# SCH_STM32_STEPMOTOR.net
KiCad netlist of a schematic drawn in Altium Designer
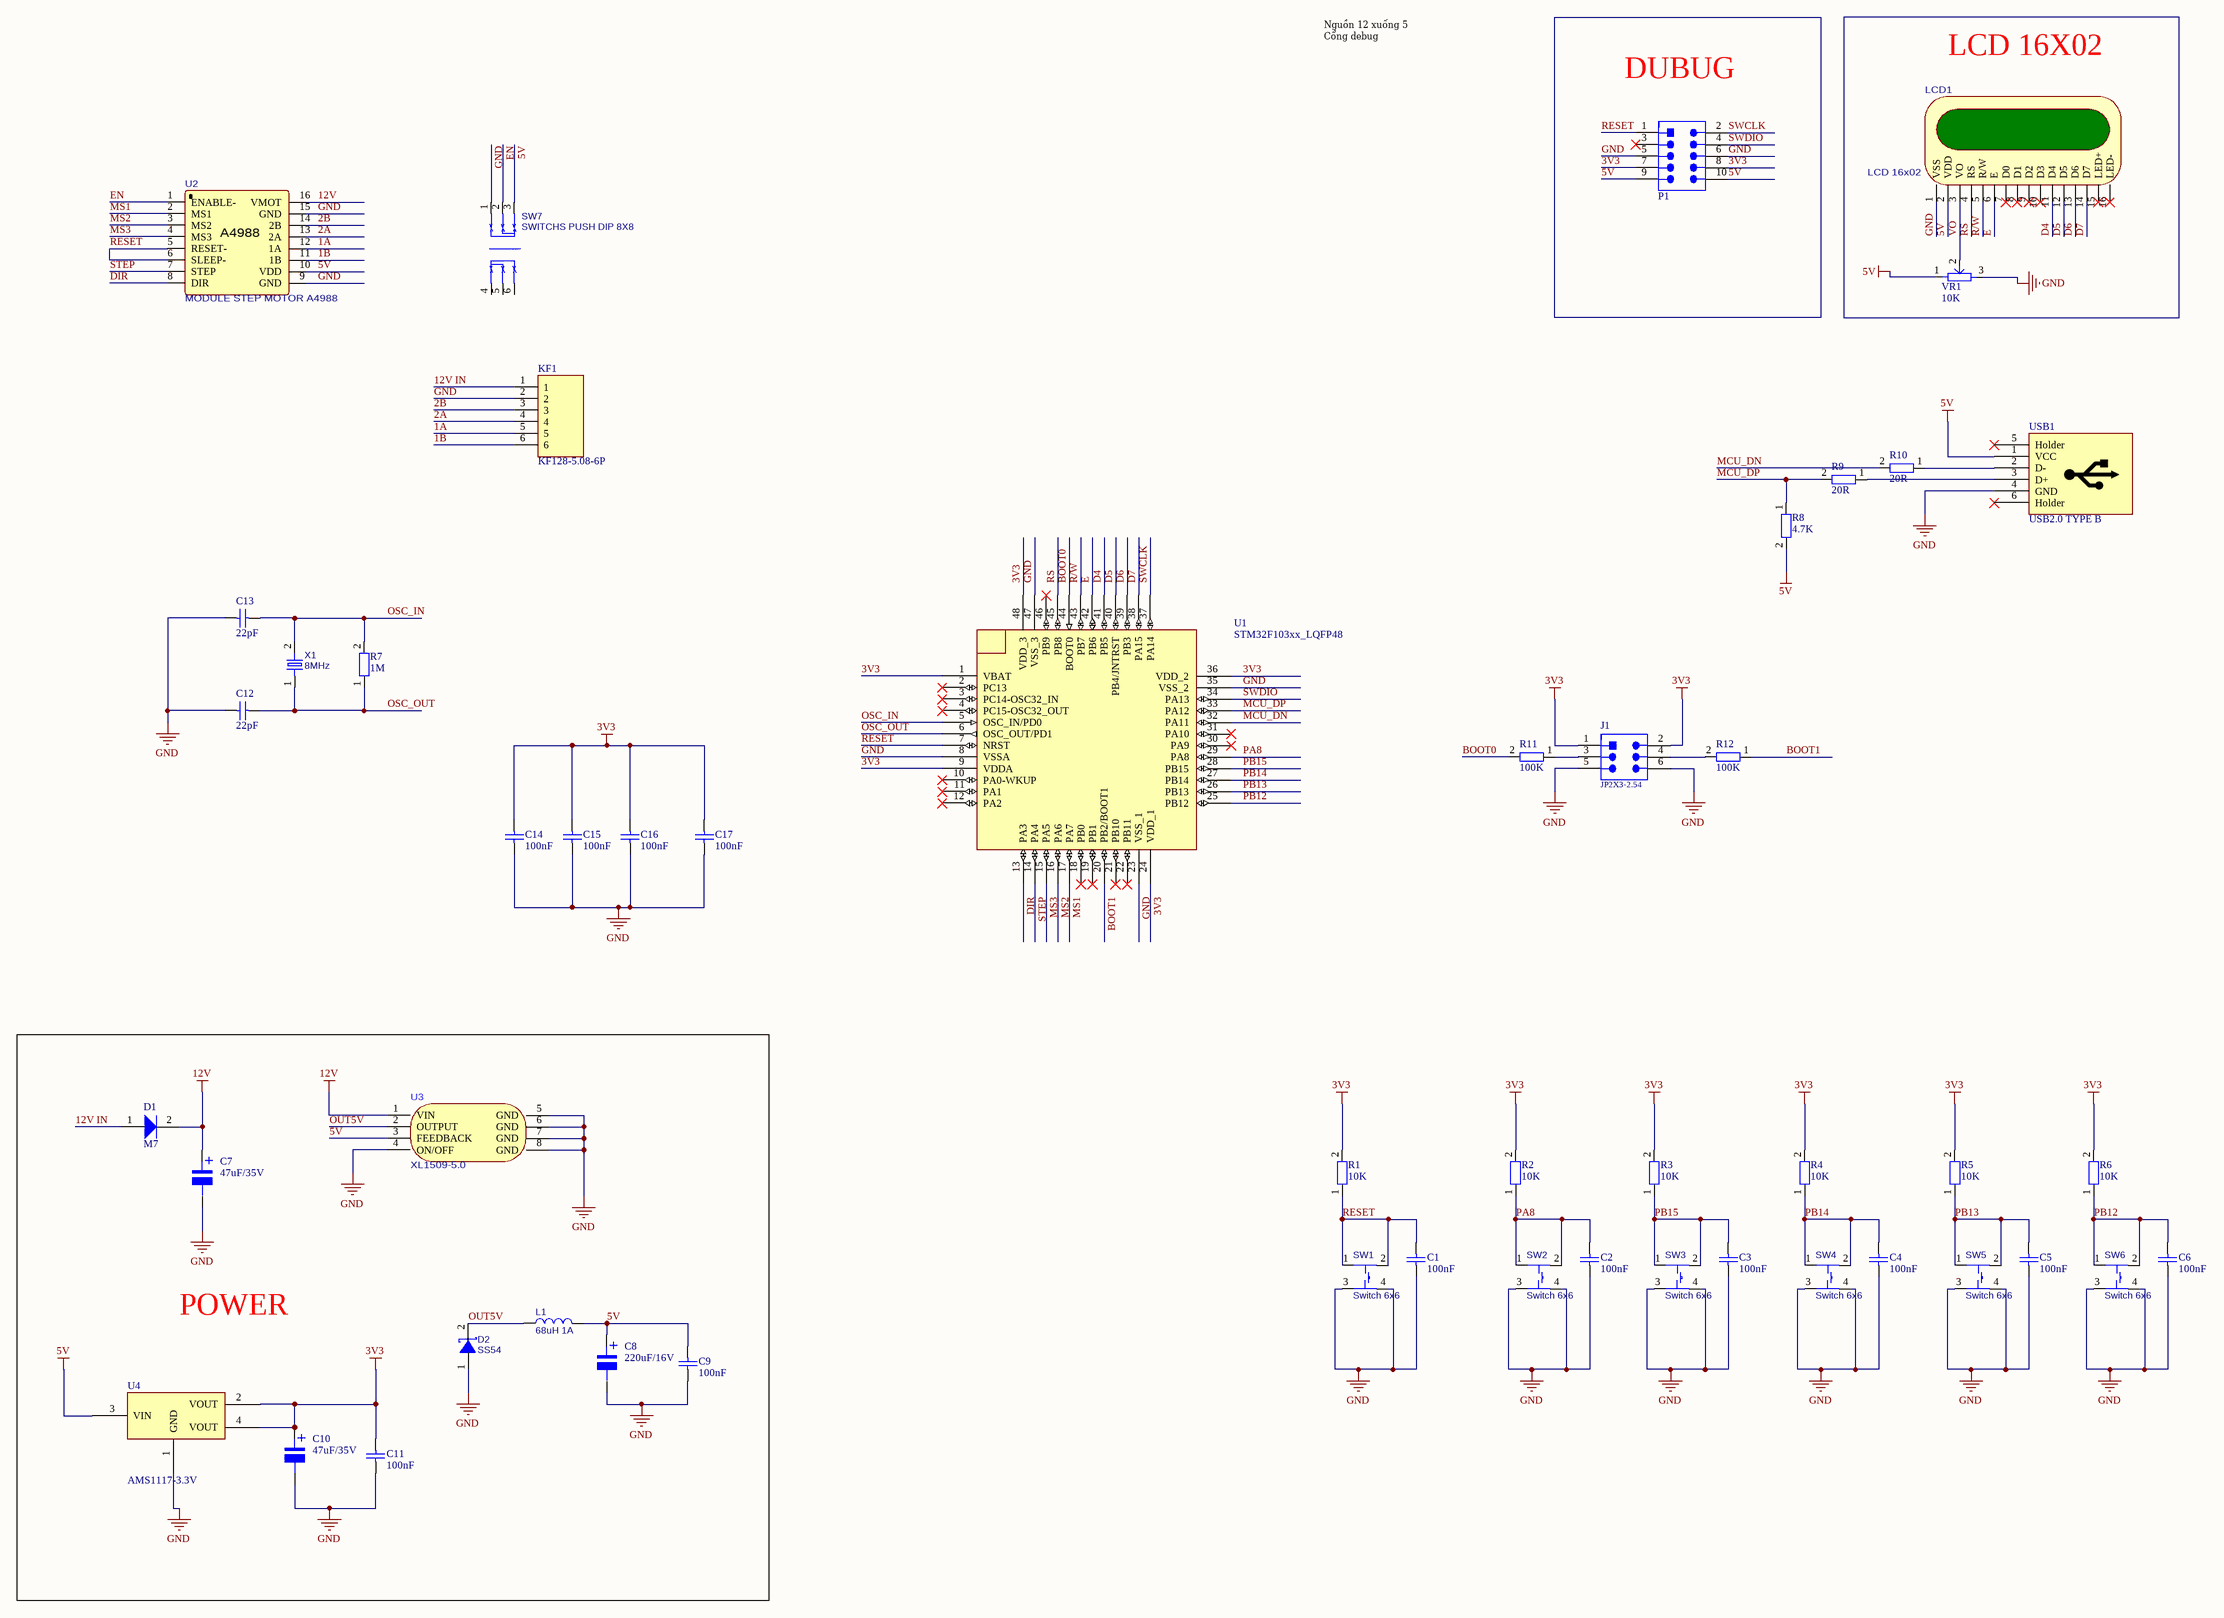
[diagram p0: SCH_STM32_STEPMOTOR.SchDoc]

(export (version "E")
  (design (tool "Eeschema 10.0.6"))
  (components
    (comp (ref "C1")
      (value "100nF")
      (footprint "CAP CERAMIC SMD 0805 TyPE 2012")
      (description "0805 Multilayer Ceramic Capacitors MLCC - SMD/SMT ROHS")
      (libsource (lib "SCH_AES_Library") (part "CAP 0805 50V 10%"))
    )
    (comp (ref "C2")
      (value "100nF")
      (footprint "CAP CERAMIC SMD 0805 TyPE 2012")
      (description "0805 Multilayer Ceramic Capacitors MLCC - SMD/SMT ROHS")
      (libsource (lib "SCH_AES_Library") (part "CAP 0805 50V 10%"))
    )
    (comp (ref "C3")
      (value "100nF")
      (footprint "CAP CERAMIC SMD 0805 TyPE 2012")
      (description "0805 Multilayer Ceramic Capacitors MLCC - SMD/SMT ROHS")
      (libsource (lib "SCH_AES_Library") (part "CAP 0805 50V 10%"))
    )
    (comp (ref "C4")
      (value "100nF")
      (footprint "CAP CERAMIC SMD 0805 TyPE 2012")
      (description "0805 Multilayer Ceramic Capacitors MLCC - SMD/SMT ROHS")
      (libsource (lib "SCH_AES_Library") (part "CAP 0805 50V 10%"))
    )
    (comp (ref "C5")
      (value "100nF")
      (footprint "CAP CERAMIC SMD 0805 TyPE 2012")
      (description "0805 Multilayer Ceramic Capacitors MLCC - SMD/SMT ROHS")
      (libsource (lib "SCH_AES_Library") (part "CAP 0805 50V 10%"))
    )
    (comp (ref "C6")
      (value "100nF")
      (footprint "CAP CERAMIC SMD 0805 TyPE 2012")
      (description "0805 Multilayer Ceramic Capacitors MLCC - SMD/SMT ROHS")
      (libsource (lib "SCH_AES_Library") (part "CAP 0805 50V 10%"))
    )
    (comp (ref "C7")
      (value "47uF/35V")
      (footprint "Cap Alum SMD 6.3x5.4 TYPE D")
      (description "Aluminum Electrolytic Capacitors - SMD ROHS")
      (libsource (lib "SCH_AES_Library") (part "CAP ALUMINUM SMD"))
    )
    (comp (ref "C8")
      (value "220uF/16V")
      (footprint "Cap Alum SMD 6.3x7.7 TYPE D8")
      (description "Aluminum Electrolytic Capacitors - SMD ROHS")
      (libsource (lib "SCH_AES_Library") (part "CAP ALUMINUM SMD"))
    )
    (comp (ref "C9")
      (value "100nF")
      (footprint "CAP CERAMIC SMD 0805 TyPE 2012")
      (description "0805 Multilayer Ceramic Capacitors MLCC - SMD/SMT ROHS")
      (libsource (lib "SCH_AES_Library") (part "CAP 0805 50V 10%"))
    )
    (comp (ref "C10")
      (value "47uF/35V")
      (footprint "Cap Alum SMD 6.3x5.4 TYPE D")
      (description "Aluminum Electrolytic Capacitors - SMD ROHS")
      (libsource (lib "SCH_AES_Library") (part "CAP ALUMINUM SMD"))
    )
    (comp (ref "C11")
      (value "100nF")
      (footprint "CAP CERAMIC SMD 0805 TyPE 2012")
      (description "0805 Multilayer Ceramic Capacitors MLCC - SMD/SMT ROHS")
      (libsource (lib "SCH_AES_Library") (part "CAP 0805 50V 10%"))
    )
    (comp (ref "C12")
      (value "22pF")
      (footprint "CAP CERAMIC SMD 0805 TyPE 2012")
      (description "0805 Multilayer Ceramic Capacitors MLCC - SMD/SMT ROHS")
      (libsource (lib "SCH_AES_Library") (part "CAP 0805 50V 10%"))
    )
    (comp (ref "C13")
      (value "22pF")
      (footprint "CAP CERAMIC SMD 0805 TyPE 2012")
      (description "0805 Multilayer Ceramic Capacitors MLCC - SMD/SMT ROHS")
      (libsource (lib "SCH_AES_Library") (part "CAP 0805 50V 10%"))
    )
    (comp (ref "C14")
      (value "100nF")
      (footprint "CAP CERAMIC SMD 0805 TyPE 2012")
      (description "0805 Multilayer Ceramic Capacitors MLCC - SMD/SMT ROHS")
      (libsource (lib "SCH_AES_Library") (part "CAP 0805 50V 10%"))
    )
    (comp (ref "C15")
      (value "100nF")
      (footprint "CAP CERAMIC SMD 0805 TyPE 2012")
      (description "0805 Multilayer Ceramic Capacitors MLCC - SMD/SMT ROHS")
      (libsource (lib "SCH_AES_Library") (part "CAP 0805 50V 10%"))
    )
    (comp (ref "C16")
      (value "100nF")
      (footprint "CAP CERAMIC SMD 0805 TyPE 2012")
      (description "0805 Multilayer Ceramic Capacitors MLCC - SMD/SMT ROHS")
      (libsource (lib "SCH_AES_Library") (part "CAP 0805 50V 10%"))
    )
    (comp (ref "C17")
      (value "100nF")
      (footprint "CAP CERAMIC SMD 0805 TyPE 2012")
      (description "0805 Multilayer Ceramic Capacitors MLCC - SMD/SMT ROHS")
      (libsource (lib "SCH_AES_Library") (part "CAP 0805 50V 10%"))
    )
    (comp (ref "D1")
      (value "M7")
      (footprint "DIODE SMD SMA")
      (description "1A 1kV Diodes - General Purpose ROHS")
      (libsource (lib "SCH_AES_Library") (part "DIODE SMD 1N4007"))
    )
    (comp (ref "D2")
      (value "SS54")
      (footprint "DO-214AC(SMA)")
      (description "500uA@40V 40V 550mV@5A 5A SMA(DO-214AC) Schottky Barrier Diodes (SBD) ROHS")
      (fields
        (field (name "BOM_SUPPLIER PART") "C478723")
        (field (name "BOM_MANUFACTURER PART") "SS34")
        (field (name "CONTRIBUTOR") "LCSC")
      )
      (libsource (lib "SCH_AES_Library") (part "DIODE SMD SS54"))
    )
    (comp (ref "J1")
      (value "JP2X3-2.54")
      (footprint "CONNECTORS MALE HEADERS 2X3 2.54 TYPE STRAIGHT")
      (description "WR-PHD Pin Header, THT, pitch 2.54mm, Dual Row, Angled, 6p")
      (fields
        (field (name "MANUFACTURER PART NUMBER") "61300621021")
        (field (name "MANUFACTURER") "Wurth Elektronik")
      )
      (libsource (lib "SCH_AES_Library") (part "CONNECTORS MALE HEADERS 2X3 2.54"))
    )
    (comp (ref "KF1")
      (value "KF128-5.08-6P")
      (footprint "CONNECTORS SCREW TERMINAL KF128-5.08-6P")
      (description "2~24 Poles, Screw Type, Horizontal, 5.08 Pitch, 24~12 _AWG_, Terminal Block Connector")
      (fields (field (name "MP") "TB004-508-06GR"))
      (libsource (lib "SCH_AES_Library") (part "CONNECTORS SCREW TERMINAL KF128-5.08-6P"))
    )
    (comp (ref "L1")
      (value "68uH 1A")
      (footprint "INDUCTOS POWER SMD CDRH")
      (fields
        (field (name "BOM_SUPPLIER PART") "C578001")
        (field (name "BOM_MANUFACTURER PART") "SCHF160808H47NJT")
        (field (name "CONTRIBUTOR") "LCSC")
      )
      (libsource (lib "SCH_AES_Library") (part "INDUCTORS SMD"))
    )
    (comp (ref "LCD1")
      (value "LCD 16x02")
      (footprint "LCD DISPLAYS 16X2")
      (description "LCD Displays Modules 16x02 5V ROHS")
      (libsource (lib "SCH_AES_Library") (part "LCD DISPLAYS 16x02"))
    )
    (comp (ref "P1")
      (value "IDE 5X2")
      (footprint "CONNECTORS IDC PUSH PULL 5x2 TYPE STRAIGHT")
      (description "WR-BHD Box Header, Male, pitch 2.54mm, SMT, Straight, 10p")
      (fields
        (field (name "MANUFACTURER") "Wurth Elektronik")
        (field (name "MANUFACTURER PART NUMBER") "61201020621")
      )
      (libsource (lib "SCH_AES_Library") (part "CONNECTORS IDC 5X2"))
    )
    (comp (ref "R1")
      (value "10K")
      (footprint "RES CHIPS SMD 0805 TYPE 2012")
      (description "±1% - Chip Resistor - Surface Mount ROHS")
      (libsource (lib "SCH_AES_Library") (part "RES 0805 1%"))
    )
    (comp (ref "R2")
      (value "10K")
      (footprint "RES CHIPS SMD 0805 TYPE 2012")
      (description "±1% - Chip Resistor - Surface Mount ROHS")
      (libsource (lib "SCH_AES_Library") (part "RES 0805 1%"))
    )
    (comp (ref "R3")
      (value "10K")
      (footprint "RES CHIPS SMD 0805 TYPE 2012")
      (description "±1% - Chip Resistor - Surface Mount ROHS")
      (libsource (lib "SCH_AES_Library") (part "RES 0805 1%"))
    )
    (comp (ref "R4")
      (value "10K")
      (footprint "RES CHIPS SMD 0805 TYPE 2012")
      (description "±1% - Chip Resistor - Surface Mount ROHS")
      (libsource (lib "SCH_AES_Library") (part "RES 0805 1%"))
    )
    (comp (ref "R5")
      (value "10K")
      (footprint "RES CHIPS SMD 0805 TYPE 2012")
      (description "±1% - Chip Resistor - Surface Mount ROHS")
      (libsource (lib "SCH_AES_Library") (part "RES 0805 1%"))
    )
    (comp (ref "R6")
      (value "10K")
      (footprint "RES CHIPS SMD 0805 TYPE 2012")
      (description "±1% - Chip Resistor - Surface Mount ROHS")
      (libsource (lib "SCH_AES_Library") (part "RES 0805 1%"))
    )
    (comp (ref "R7")
      (value "1M")
      (footprint "RES CHIPS SMD 0805 TYPE 2012")
      (description "±1% - Chip Resistor - Surface Mount ROHS")
      (libsource (lib "SCH_AES_Library") (part "RES 0805 1%"))
    )
    (comp (ref "R8")
      (value "4.7K")
      (footprint "RES CHIPS SMD 0805 TYPE 2012")
      (description "±1% - Chip Resistor - Surface Mount ROHS")
      (libsource (lib "SCH_AES_Library") (part "RES 0805 1%"))
    )
    (comp (ref "R9")
      (value "20R")
      (footprint "RES CHIPS SMD 0805 TYPE 2012")
      (description "±1% - Chip Resistor - Surface Mount ROHS")
      (libsource (lib "SCH_AES_Library") (part "RES 0805 1%"))
    )
    (comp (ref "R10")
      (value "20R")
      (footprint "RES CHIPS SMD 0805 TYPE 2012")
      (description "±1% - Chip Resistor - Surface Mount ROHS")
      (libsource (lib "SCH_AES_Library") (part "RES 0805 1%"))
    )
    (comp (ref "R11")
      (value "100K")
      (footprint "RES CHIPS SMD 0805 TYPE 2012")
      (description "±1% - Chip Resistor - Surface Mount ROHS")
      (libsource (lib "SCH_AES_Library") (part "RES 0805 1%"))
    )
    (comp (ref "R12")
      (value "100K")
      (footprint "RES CHIPS SMD 0805 TYPE 2012")
      (description "±1% - Chip Resistor - Surface Mount ROHS")
      (libsource (lib "SCH_AES_Library") (part "RES 0805 1%"))
    )
    (comp (ref "SW1")
      (value "Switch 6x6")
      (footprint "SWITCHES TACTILE DIP 6X6x5 mm")
      (fields
        (field (name "BOM_MANUFACTURER PART") "B3F-1000")
        (field (name "BOM_SUPPLIER PART") "C93157")
        (field (name "CONTRIBUTOR") "LCSC")
      )
      (libsource (lib "SCH_AES_Library") (part "Switches Tactile 6x6mm"))
    )
    (comp (ref "SW2")
      (value "Switch 6x6")
      (footprint "SWITCHES TACTILE DIP 6X6x5 mm")
      (fields
        (field (name "BOM_MANUFACTURER PART") "B3F-1000")
        (field (name "BOM_SUPPLIER PART") "C93157")
        (field (name "CONTRIBUTOR") "LCSC")
      )
      (libsource (lib "SCH_AES_Library") (part "Switches Tactile 6x6mm"))
    )
    (comp (ref "SW3")
      (value "Switch 6x6")
      (footprint "SWITCHES TACTILE DIP 6X6x5 mm")
      (fields
        (field (name "BOM_MANUFACTURER PART") "B3F-1000")
        (field (name "BOM_SUPPLIER PART") "C93157")
        (field (name "CONTRIBUTOR") "LCSC")
      )
      (libsource (lib "SCH_AES_Library") (part "Switches Tactile 6x6mm"))
    )
    (comp (ref "SW4")
      (value "Switch 6x6")
      (footprint "SWITCHES TACTILE DIP 6X6x5 mm")
      (fields
        (field (name "BOM_MANUFACTURER PART") "B3F-1000")
        (field (name "BOM_SUPPLIER PART") "C93157")
        (field (name "CONTRIBUTOR") "LCSC")
      )
      (libsource (lib "SCH_AES_Library") (part "Switches Tactile 6x6mm"))
    )
    (comp (ref "SW5")
      (value "Switch 6x6")
      (footprint "SWITCHES TACTILE DIP 6X6x5 mm")
      (fields
        (field (name "BOM_MANUFACTURER PART") "B3F-1000")
        (field (name "BOM_SUPPLIER PART") "C93157")
        (field (name "CONTRIBUTOR") "LCSC")
      )
      (libsource (lib "SCH_AES_Library") (part "Switches Tactile 6x6mm"))
    )
    (comp (ref "SW6")
      (value "Switch 6x6")
      (footprint "SWITCHES TACTILE DIP 6X6x5 mm")
      (fields
        (field (name "BOM_MANUFACTURER PART") "B3F-1000")
        (field (name "BOM_SUPPLIER PART") "C93157")
        (field (name "CONTRIBUTOR") "LCSC")
      )
      (libsource (lib "SCH_AES_Library") (part "Switches Tactile 6x6mm"))
    )
    (comp (ref "SW7")
      (value "SWITCHS PUSH DIP 8X8")
      (footprint "SWITCHES PUSH DIP 8X8 mm")
      (fields
        (field (name "BOM_SUPPLIER PART") "C318861")
        (field (name "BOM_MANUFACTURER PART") "XKB8080-W")
        (field (name "CONTRIBUTOR") "LCSC")
      )
      (libsource (lib "SCH_AES_Library") (part "SWITCHS PUSH DIP 8X8"))
    )
    (comp (ref "U1")
      (value "STM32F103xx_LQFP48")
      (footprint "LQFP-48")
      (fields (field (name "PUBLISHER") "Altium Limited"))
      (libsource (lib "SCH_AES_Library") (part "MCU_STM32F103xx"))
    )
    (comp (ref "U2")
      (value "MODULE STEP MOTOR A4988")
      (footprint "MODULES STEP MOTOR A4988")
      (description "MODULES STEP MOTOR A4988")
      (libsource (lib "SCH_AES_Library") (part "MODULE STEPMOTOR A4988"))
    )
    (comp (ref "U3")
      (value "XL1509-5.0")
      (footprint "SOP-8")
      (description "SOP-8 DC-DC Converters ROHS")
      (libsource (lib "SCH_AES_Library") (part "POWER CONVERTER XL1509-5.0"))
    )
    (comp (ref "U4")
      (value "AMS1117-3.3V")
      (footprint "SOT-223")
      (description "800mA 1.4V@(1A) Fixed 3.3V~3.3V Positive 1 18V SOT-223 Linear Voltage Regulators (LDO) ROHS")
      (libsource (lib "SCH_AES_Library") (part "POWER CONVERTERS AMS117-3V3"))
    )
    (comp (ref "USB1")
      (value "USB2.0 TYPE B")
      (footprint "CONNECTORS HOLD USB2.0 TYPE B SHRUODED")
      (libsource (lib "SCH_AES_Library") (part "CONNECTORS USB 2.0 DIP TYPE B"))
    )
    (comp (ref "VR1")
      (value "10K")
      (footprint "RES VARIABLE HOLE 3362P")
      (description "Plugin Variable Resistors/Potentiometers ROHS")
      (libsource (lib "SCH_AES_Library") (part "RES VARIABLE DIP"))
    )
    (comp (ref "X1")
      (value "8MHz")
      (footprint "CRYSTALS HOLD HC-49S TYPE 2P")
      (description "Crystals ROHS")
      (fields
        (field (name "BOM_SUPPLIER PART") "C295072")
        (field (name "BOM_MANUFACTURER PART") "XIHCELNANF-12MHZ")
        (field (name "CONTRIBUTOR") "LCSC")
      )
      (libsource (lib "SCH_AES_Library") (part "CRYSTALS 2P"))
    )
  )
  (nets
    (net (code "1") (name "/1A") (class "Default")
      (node (ref "KF1") (pin "5") (pinfunction "5_5") (pintype "passive"))
      (node (ref "U2") (pin "12") (pinfunction "1A_12") (pintype "passive"))
    )
    (net (code "2") (name "/1B") (class "Default")
      (node (ref "KF1") (pin "6") (pinfunction "6_6") (pintype "passive"))
      (node (ref "U2") (pin "11") (pinfunction "1B_11") (pintype "passive"))
    )
    (net (code "3") (name "/2A") (class "Default")
      (node (ref "KF1") (pin "4") (pinfunction "4_4") (pintype "passive"))
      (node (ref "U2") (pin "13") (pinfunction "2A_13") (pintype "passive"))
    )
    (net (code "4") (name "/2B") (class "Default")
      (node (ref "KF1") (pin "3") (pinfunction "3_3") (pintype "passive"))
      (node (ref "U2") (pin "14") (pinfunction "2B_14") (pintype "passive"))
    )
    (net (code "5") (name "/12V IN") (class "Default")
      (node (ref "D1") (pin "1") (pinfunction "A_1") (pintype "passive"))
      (node (ref "KF1") (pin "1") (pinfunction "1_1") (pintype "passive"))
    )
    (net (code "6") (name "/BOOT0") (class "Default")
      (node (ref "R11") (pin "2") (pinfunction "2_2") (pintype "passive"))
      (node (ref "U1") (pin "44") (pinfunction "BOOT0_44") (pintype "input"))
    )
    (net (code "7") (name "/BOOT1") (class "Default")
      (node (ref "R12") (pin "1") (pinfunction "1_1") (pintype "passive"))
      (node (ref "U1") (pin "20") (pinfunction "PB2/BOOT1_20") (pintype "bidirectional"))
    )
    (net (code "8") (name "/D4") (class "Default")
      (node (ref "LCD1") (pin "11") (pinfunction "D4_11") (pintype "passive"))
      (node (ref "U1") (pin "41") (pinfunction "PB5_41") (pintype "bidirectional"))
    )
    (net (code "9") (name "/D5") (class "Default")
      (node (ref "LCD1") (pin "12") (pinfunction "D5_12") (pintype "passive"))
      (node (ref "U1") (pin "40") (pinfunction "PB4/JNTRST_40") (pintype "bidirectional"))
    )
    (net (code "10") (name "/D6") (class "Default")
      (node (ref "LCD1") (pin "13") (pinfunction "D6_13") (pintype "passive"))
      (node (ref "U1") (pin "39") (pinfunction "PB3_39") (pintype "bidirectional"))
    )
    (net (code "11") (name "/D7") (class "Default")
      (node (ref "LCD1") (pin "14") (pinfunction "D7_14") (pintype "passive"))
      (node (ref "U1") (pin "38") (pinfunction "PA15_38") (pintype "bidirectional"))
    )
    (net (code "12") (name "/DIR") (class "Default")
      (node (ref "U1") (pin "13") (pinfunction "PA3_13") (pintype "bidirectional"))
      (node (ref "U2") (pin "8") (pinfunction "DIR_8") (pintype "passive"))
    )
    (net (code "13") (name "/E") (class "Default")
      (node (ref "LCD1") (pin "6") (pinfunction "E_6") (pintype "passive"))
      (node (ref "U1") (pin "42") (pinfunction "PB6_42") (pintype "bidirectional"))
    )
    (net (code "14") (name "/EN") (class "Default")
      (node (ref "SW7") (pin "2") (pinfunction "2_2") (pintype "passive"))
      (node (ref "U2") (pin "1") (pinfunction "ENABLE-_1") (pintype "passive"))
    )
    (net (code "15") (name "/MCU_DN") (class "Default")
      (node (ref "R10") (pin "2") (pinfunction "2_2") (pintype "passive"))
      (node (ref "U1") (pin "32") (pinfunction "PA11_32") (pintype "bidirectional"))
    )
    (net (code "16") (name "/MCU_DP") (class "Default")
      (node (ref "R8") (pin "1") (pinfunction "1_1") (pintype "passive"))
      (node (ref "R9") (pin "2") (pinfunction "2_2") (pintype "passive"))
      (node (ref "U1") (pin "33") (pinfunction "PA12_33") (pintype "bidirectional"))
    )
    (net (code "17") (name "/MS1") (class "Default")
      (node (ref "U1") (pin "17") (pinfunction "PA7_17") (pintype "bidirectional"))
      (node (ref "U2") (pin "2") (pinfunction "MS1_2") (pintype "passive"))
    )
    (net (code "18") (name "/MS2") (class "Default")
      (node (ref "U1") (pin "16") (pinfunction "PA6_16") (pintype "bidirectional"))
      (node (ref "U2") (pin "3") (pinfunction "MS2_3") (pintype "passive"))
    )
    (net (code "19") (name "/MS3") (class "Default")
      (node (ref "U1") (pin "15") (pinfunction "PA5_15") (pintype "bidirectional"))
      (node (ref "U2") (pin "4") (pinfunction "MS3_4") (pintype "passive"))
    )
    (net (code "20") (name "/OSC_IN") (class "Default")
      (node (ref "C13") (pin "1") (pinfunction "1_1") (pintype "passive"))
      (node (ref "R7") (pin "2") (pinfunction "2_2") (pintype "passive"))
      (node (ref "U1") (pin "5") (pinfunction "OSC_IN/PD0_5") (pintype "input"))
      (node (ref "X1") (pin "2") (pinfunction "2_2") (pintype "passive"))
    )
    (net (code "21") (name "/OSC_OUT") (class "Default")
      (node (ref "C12") (pin "1") (pinfunction "1_1") (pintype "passive"))
      (node (ref "R7") (pin "1") (pinfunction "1_1") (pintype "passive"))
      (node (ref "U1") (pin "6") (pinfunction "OSC_OUT/PD1_6") (pintype "output"))
      (node (ref "X1") (pin "1") (pinfunction "1_1") (pintype "passive"))
    )
    (net (code "22") (name "/OUT5V") (class "Default")
      (node (ref "D2") (pin "2") (pinfunction "K_2") (pintype "passive"))
      (node (ref "L1") (pin "1") (pinfunction "1_1") (pintype "passive"))
      (node (ref "U3") (pin "2") (pinfunction "OUTPUT_2") (pintype "passive"))
    )
    (net (code "23") (name "/PA8") (class "Default")
      (node (ref "C2") (pin "1") (pinfunction "1_1") (pintype "passive"))
      (node (ref "R2") (pin "1") (pinfunction "1_1") (pintype "passive"))
      (node (ref "SW2") (pin "1") (pinfunction "1_1") (pintype "passive"))
      (node (ref "SW2") (pin "2") (pinfunction "2_2") (pintype "passive"))
      (node (ref "U1") (pin "29") (pinfunction "PA8_29") (pintype "bidirectional"))
    )
    (net (code "24") (name "/PB12") (class "Default")
      (node (ref "C6") (pin "1") (pinfunction "1_1") (pintype "passive"))
      (node (ref "R6") (pin "1") (pinfunction "1_1") (pintype "passive"))
      (node (ref "SW6") (pin "1") (pinfunction "1_1") (pintype "passive"))
      (node (ref "SW6") (pin "2") (pinfunction "2_2") (pintype "passive"))
      (node (ref "U1") (pin "25") (pinfunction "PB12_25") (pintype "bidirectional"))
    )
    (net (code "25") (name "/PB13") (class "Default")
      (node (ref "C5") (pin "1") (pinfunction "1_1") (pintype "passive"))
      (node (ref "R5") (pin "1") (pinfunction "1_1") (pintype "passive"))
      (node (ref "SW5") (pin "1") (pinfunction "1_1") (pintype "passive"))
      (node (ref "SW5") (pin "2") (pinfunction "2_2") (pintype "passive"))
      (node (ref "U1") (pin "26") (pinfunction "PB13_26") (pintype "bidirectional"))
    )
    (net (code "26") (name "/PB14") (class "Default")
      (node (ref "C4") (pin "1") (pinfunction "1_1") (pintype "passive"))
      (node (ref "R4") (pin "1") (pinfunction "1_1") (pintype "passive"))
      (node (ref "SW4") (pin "1") (pinfunction "1_1") (pintype "passive"))
      (node (ref "SW4") (pin "2") (pinfunction "2_2") (pintype "passive"))
      (node (ref "U1") (pin "27") (pinfunction "PB14_27") (pintype "bidirectional"))
    )
    (net (code "27") (name "/PB15") (class "Default")
      (node (ref "C3") (pin "1") (pinfunction "1_1") (pintype "passive"))
      (node (ref "R3") (pin "1") (pinfunction "1_1") (pintype "passive"))
      (node (ref "SW3") (pin "1") (pinfunction "1_1") (pintype "passive"))
      (node (ref "SW3") (pin "2") (pinfunction "2_2") (pintype "passive"))
      (node (ref "U1") (pin "28") (pinfunction "PB15_28") (pintype "bidirectional"))
    )
    (net (code "28") (name "/RESET") (class "Default")
      (node (ref "C1") (pin "1") (pinfunction "1_1") (pintype "passive"))
      (node (ref "P1") (pin "1") (pinfunction "1_1") (pintype "passive"))
      (node (ref "R1") (pin "1") (pinfunction "1_1") (pintype "passive"))
      (node (ref "SW1") (pin "1") (pinfunction "1_1") (pintype "passive"))
      (node (ref "SW1") (pin "2") (pinfunction "2_2") (pintype "passive"))
      (node (ref "U1") (pin "7") (pinfunction "NRST_7") (pintype "bidirectional"))
      (node (ref "U2") (pin "5") (pinfunction "RESET-_5") (pintype "passive"))
      (node (ref "U2") (pin "6") (pinfunction "SLEEP-_6") (pintype "passive"))
    )
    (net (code "29") (name "/RS") (class "Default")
      (node (ref "LCD1") (pin "4") (pinfunction "RS_4") (pintype "passive"))
      (node (ref "U1") (pin "45") (pinfunction "PB8_45") (pintype "bidirectional"))
    )
    (net (code "30") (name "/R{slash}W") (class "Default")
      (node (ref "LCD1") (pin "5") (pinfunction "R/W_5") (pintype "passive"))
      (node (ref "U1") (pin "43") (pinfunction "PB7_43") (pintype "bidirectional"))
    )
    (net (code "31") (name "/STEP") (class "Default")
      (node (ref "U1") (pin "14") (pinfunction "PA4_14") (pintype "bidirectional"))
      (node (ref "U2") (pin "7") (pinfunction "STEP_7") (pintype "passive"))
    )
    (net (code "32") (name "/SWCLK") (class "Default")
      (node (ref "P1") (pin "2") (pinfunction "2_2") (pintype "passive"))
      (node (ref "U1") (pin "37") (pinfunction "PA14_37") (pintype "bidirectional"))
    )
    (net (code "33") (name "/SWDIO") (class "Default")
      (node (ref "P1") (pin "4") (pinfunction "4_4") (pintype "passive"))
      (node (ref "U1") (pin "34") (pinfunction "PA13_34") (pintype "bidirectional"))
    )
    (net (code "34") (name "/VO") (class "Default")
      (node (ref "LCD1") (pin "3") (pinfunction "VO_3") (pintype "passive"))
      (node (ref "VR1") (pin "2") (pinfunction "2_2") (pintype "passive"))
    )
    (net (code "35") (name "3V3") (class "Default")
      (node (ref "C10") (pin "1") (pinfunction "1_1") (pintype "passive"))
      (node (ref "C11") (pin "1") (pinfunction "1_1") (pintype "passive"))
      (node (ref "C14") (pin "1") (pinfunction "1_1") (pintype "passive"))
      (node (ref "C15") (pin "1") (pinfunction "1_1") (pintype "passive"))
      (node (ref "C16") (pin "1") (pinfunction "1_1") (pintype "passive"))
      (node (ref "C17") (pin "1") (pinfunction "1_1") (pintype "passive"))
      (node (ref "J1") (pin "1") (pinfunction "1_1") (pintype "passive"))
      (node (ref "J1") (pin "2") (pinfunction "2_2") (pintype "passive"))
      (node (ref "P1") (pin "7") (pinfunction "7_7") (pintype "passive"))
      (node (ref "P1") (pin "8") (pinfunction "8_8") (pintype "passive"))
      (node (ref "R1") (pin "2") (pinfunction "2_2") (pintype "passive"))
      (node (ref "R2") (pin "2") (pinfunction "2_2") (pintype "passive"))
      (node (ref "R3") (pin "2") (pinfunction "2_2") (pintype "passive"))
      (node (ref "R4") (pin "2") (pinfunction "2_2") (pintype "passive"))
      (node (ref "R5") (pin "2") (pinfunction "2_2") (pintype "passive"))
      (node (ref "R6") (pin "2") (pinfunction "2_2") (pintype "passive"))
      (node (ref "U1") (pin "1") (pinfunction "VBAT_1") (pintype "power_in"))
      (node (ref "U1") (pin "24") (pinfunction "VDD_1_24") (pintype "power_in"))
      (node (ref "U1") (pin "36") (pinfunction "VDD_2_36") (pintype "power_in"))
      (node (ref "U1") (pin "48") (pinfunction "VDD_3_48") (pintype "power_in"))
      (node (ref "U1") (pin "9") (pinfunction "VDDA_9") (pintype "power_in"))
      (node (ref "U4") (pin "2") (pinfunction "VOUT_2") (pintype "passive"))
      (node (ref "U4") (pin "4") (pinfunction "VOUT_4") (pintype "passive"))
    )
    (net (code "36") (name "5V") (class "Default")
      (node (ref "C8") (pin "1") (pinfunction "1_1") (pintype "passive"))
      (node (ref "C9") (pin "1") (pinfunction "1_1") (pintype "passive"))
      (node (ref "L1") (pin "2") (pinfunction "2_2") (pintype "passive"))
      (node (ref "LCD1") (pin "2") (pinfunction "VDD_2") (pintype "passive"))
      (node (ref "P1") (pin "10") (pinfunction "10_10") (pintype "passive"))
      (node (ref "P1") (pin "9") (pinfunction "9_9") (pintype "passive"))
      (node (ref "R8") (pin "2") (pinfunction "2_2") (pintype "passive"))
      (node (ref "SW7") (pin "3") (pinfunction "3_3") (pintype "passive"))
      (node (ref "U2") (pin "10") (pinfunction "VDD_10") (pintype "passive"))
      (node (ref "U3") (pin "3") (pinfunction "FEEDBACK_3") (pintype "passive"))
      (node (ref "U4") (pin "3") (pinfunction "VIN_3") (pintype "passive"))
      (node (ref "USB1") (pin "1") (pinfunction "VCC_1") (pintype "passive"))
      (node (ref "VR1") (pin "1") (pinfunction "1_1") (pintype "passive"))
    )
    (net (code "37") (name "12V") (class "Default")
      (node (ref "C7") (pin "1") (pinfunction "1_1") (pintype "passive"))
      (node (ref "D1") (pin "2") (pinfunction "K_2") (pintype "passive"))
      (node (ref "U2") (pin "16") (pinfunction "VMOT_16") (pintype "passive"))
      (node (ref "U3") (pin "1") (pinfunction "VIN_1") (pintype "passive"))
    )
    (net (code "38") (name "GND") (class "Default")
      (node (ref "C1") (pin "2") (pinfunction "2_2") (pintype "passive"))
      (node (ref "C10") (pin "2") (pinfunction "2_2") (pintype "passive"))
      (node (ref "C11") (pin "2") (pinfunction "2_2") (pintype "passive"))
      (node (ref "C12") (pin "2") (pinfunction "2_2") (pintype "passive"))
      (node (ref "C13") (pin "2") (pinfunction "2_2") (pintype "passive"))
      (node (ref "C14") (pin "2") (pinfunction "2_2") (pintype "passive"))
      (node (ref "C15") (pin "2") (pinfunction "2_2") (pintype "passive"))
      (node (ref "C16") (pin "2") (pinfunction "2_2") (pintype "passive"))
      (node (ref "C17") (pin "2") (pinfunction "2_2") (pintype "passive"))
      (node (ref "C2") (pin "2") (pinfunction "2_2") (pintype "passive"))
      (node (ref "C3") (pin "2") (pinfunction "2_2") (pintype "passive"))
      (node (ref "C4") (pin "2") (pinfunction "2_2") (pintype "passive"))
      (node (ref "C5") (pin "2") (pinfunction "2_2") (pintype "passive"))
      (node (ref "C6") (pin "2") (pinfunction "2_2") (pintype "passive"))
      (node (ref "C7") (pin "2") (pinfunction "2_2") (pintype "passive"))
      (node (ref "C8") (pin "2") (pinfunction "2_2") (pintype "passive"))
      (node (ref "C9") (pin "2") (pinfunction "2_2") (pintype "passive"))
      (node (ref "D2") (pin "1") (pinfunction "A_1") (pintype "passive"))
      (node (ref "J1") (pin "5") (pinfunction "5_5") (pintype "passive"))
      (node (ref "J1") (pin "6") (pinfunction "6_6") (pintype "passive"))
      (node (ref "KF1") (pin "2") (pinfunction "2_2") (pintype "passive"))
      (node (ref "LCD1") (pin "1") (pinfunction "VSS_1") (pintype "passive"))
      (node (ref "P1") (pin "5") (pinfunction "5_5") (pintype "passive"))
      (node (ref "P1") (pin "6") (pinfunction "6_6") (pintype "passive"))
      (node (ref "SW1") (pin "3") (pinfunction "3_3") (pintype "passive"))
      (node (ref "SW1") (pin "4") (pinfunction "4_4") (pintype "passive"))
      (node (ref "SW2") (pin "3") (pinfunction "3_3") (pintype "passive"))
      (node (ref "SW2") (pin "4") (pinfunction "4_4") (pintype "passive"))
      (node (ref "SW3") (pin "3") (pinfunction "3_3") (pintype "passive"))
      (node (ref "SW3") (pin "4") (pinfunction "4_4") (pintype "passive"))
      (node (ref "SW4") (pin "3") (pinfunction "3_3") (pintype "passive"))
      (node (ref "SW4") (pin "4") (pinfunction "4_4") (pintype "passive"))
      (node (ref "SW5") (pin "3") (pinfunction "3_3") (pintype "passive"))
      (node (ref "SW5") (pin "4") (pinfunction "4_4") (pintype "passive"))
      (node (ref "SW6") (pin "3") (pinfunction "3_3") (pintype "passive"))
      (node (ref "SW6") (pin "4") (pinfunction "4_4") (pintype "passive"))
      (node (ref "SW7") (pin "1") (pinfunction "1_1") (pintype "passive"))
      (node (ref "U1") (pin "23") (pinfunction "VSS_1_23") (pintype "power_in"))
      (node (ref "U1") (pin "35") (pinfunction "VSS_2_35") (pintype "power_in"))
      (node (ref "U1") (pin "47") (pinfunction "VSS_3_47") (pintype "power_in"))
      (node (ref "U1") (pin "8") (pinfunction "VSSA_8") (pintype "power_in"))
      (node (ref "U2") (pin "15") (pinfunction "GND_15") (pintype "passive"))
      (node (ref "U2") (pin "9") (pinfunction "GND_9") (pintype "passive"))
      (node (ref "U3") (pin "4") (pinfunction "ON/OFF_4") (pintype "passive"))
      (node (ref "U3") (pin "5") (pinfunction "GND_5") (pintype "passive"))
      (node (ref "U3") (pin "6") (pinfunction "GND_6") (pintype "passive"))
      (node (ref "U3") (pin "7") (pinfunction "GND_7") (pintype "passive"))
      (node (ref "U3") (pin "8") (pinfunction "GND_8") (pintype "passive"))
      (node (ref "U4") (pin "1") (pinfunction "GND_1") (pintype "passive"))
      (node (ref "USB1") (pin "4") (pinfunction "GND_4") (pintype "passive"))
      (node (ref "VR1") (pin "3") (pinfunction "3_3") (pintype "passive"))
    )
    (net (code "39") (name "Net-(J1-Pad3)") (class "Default")
      (node (ref "J1") (pin "3") (pinfunction "3_3") (pintype "passive"))
      (node (ref "R11") (pin "1") (pinfunction "1_1") (pintype "passive"))
    )
    (net (code "40") (name "Net-(J1-Pad4)") (class "Default")
      (node (ref "J1") (pin "4") (pinfunction "4_4") (pintype "passive"))
      (node (ref "R12") (pin "2") (pinfunction "2_2") (pintype "passive"))
    )
    (net (code "41") (name "Net-(USB1-D+)") (class "Default")
      (node (ref "R9") (pin "1") (pinfunction "1_1") (pintype "passive"))
      (node (ref "USB1") (pin "3") (pinfunction "D+_3") (pintype "passive"))
    )
    (net (code "42") (name "Net-(USB1-D-)") (class "Default")
      (node (ref "R10") (pin "1") (pinfunction "1_1") (pintype "passive"))
      (node (ref "USB1") (pin "2") (pinfunction "D-_2") (pintype "passive"))
    )
    (net (code "43") (name "unconnected-(LCD1-D0-Pad7)") (class "Default")
      (node (ref "LCD1") (pin "7") (pinfunction "D0_7") (pintype "passive+no_connect"))
    )
    (net (code "44") (name "unconnected-(LCD1-D1-Pad8)") (class "Default")
      (node (ref "LCD1") (pin "8") (pinfunction "D1_8") (pintype "passive+no_connect"))
    )
    (net (code "45") (name "unconnected-(LCD1-D2-Pad9)") (class "Default")
      (node (ref "LCD1") (pin "9") (pinfunction "D2_9") (pintype "passive+no_connect"))
    )
    (net (code "46") (name "unconnected-(LCD1-D3-Pad10)") (class "Default")
      (node (ref "LCD1") (pin "10") (pinfunction "D3_10") (pintype "passive+no_connect"))
    )
    (net (code "47") (name "unconnected-(LCD1-LED+-Pad15)") (class "Default")
      (node (ref "LCD1") (pin "15") (pinfunction "LED+_15") (pintype "passive+no_connect"))
    )
    (net (code "48") (name "unconnected-(LCD1-LED--Pad16)") (class "Default")
      (node (ref "LCD1") (pin "16") (pinfunction "LED-_16") (pintype "passive+no_connect"))
    )
    (net (code "49") (name "unconnected-(P1-Pad3)") (class "Default")
      (node (ref "P1") (pin "3") (pinfunction "3_3") (pintype "passive+no_connect"))
    )
    (net (code "50") (name "unconnected-(SW7-Pad4)") (class "Default")
      (node (ref "SW7") (pin "4") (pinfunction "4_4") (pintype "passive"))
    )
    (net (code "51") (name "unconnected-(SW7-Pad5)") (class "Default")
      (node (ref "SW7") (pin "5") (pinfunction "5_5") (pintype "passive"))
    )
    (net (code "52") (name "unconnected-(SW7-Pad6)") (class "Default")
      (node (ref "SW7") (pin "6") (pinfunction "6_6") (pintype "passive"))
    )
    (net (code "53") (name "unconnected-(U1-PA0-WKUP-Pad10)") (class "Default")
      (node (ref "U1") (pin "10") (pinfunction "PA0-WKUP_10") (pintype "bidirectional+no_connect"))
    )
    (net (code "54") (name "unconnected-(U1-PA1-Pad11)") (class "Default")
      (node (ref "U1") (pin "11") (pinfunction "PA1_11") (pintype "bidirectional+no_connect"))
    )
    (net (code "55") (name "unconnected-(U1-PA2-Pad12)") (class "Default")
      (node (ref "U1") (pin "12") (pinfunction "PA2_12") (pintype "bidirectional+no_connect"))
    )
    (net (code "56") (name "unconnected-(U1-PA9-Pad30)") (class "Default")
      (node (ref "U1") (pin "30") (pinfunction "PA9_30") (pintype "bidirectional+no_connect"))
    )
    (net (code "57") (name "unconnected-(U1-PA10-Pad31)") (class "Default")
      (node (ref "U1") (pin "31") (pinfunction "PA10_31") (pintype "bidirectional+no_connect"))
    )
    (net (code "58") (name "unconnected-(U1-PB0-Pad18)") (class "Default")
      (node (ref "U1") (pin "18") (pinfunction "PB0_18") (pintype "bidirectional+no_connect"))
    )
    (net (code "59") (name "unconnected-(U1-PB1-Pad19)") (class "Default")
      (node (ref "U1") (pin "19") (pinfunction "PB1_19") (pintype "bidirectional+no_connect"))
    )
    (net (code "60") (name "unconnected-(U1-PB9-Pad46)") (class "Default")
      (node (ref "U1") (pin "46") (pinfunction "PB9_46") (pintype "bidirectional+no_connect"))
    )
    (net (code "61") (name "unconnected-(U1-PB10-Pad21)") (class "Default")
      (node (ref "U1") (pin "21") (pinfunction "PB10_21") (pintype "bidirectional+no_connect"))
    )
    (net (code "62") (name "unconnected-(U1-PB11-Pad22)") (class "Default")
      (node (ref "U1") (pin "22") (pinfunction "PB11_22") (pintype "bidirectional+no_connect"))
    )
    (net (code "63") (name "unconnected-(U1-PC13-Pad2)") (class "Default")
      (node (ref "U1") (pin "2") (pinfunction "PC13_2") (pintype "bidirectional+no_connect"))
    )
    (net (code "64") (name "unconnected-(U1-PC14-OSC32_IN-Pad3)") (class "Default")
      (node (ref "U1") (pin "3") (pinfunction "PC14-OSC32_IN_3") (pintype "bidirectional+no_connect"))
    )
    (net (code "65") (name "unconnected-(U1-PC15-OSC32_OUT-Pad4)") (class "Default")
      (node (ref "U1") (pin "4") (pinfunction "PC15-OSC32_OUT_4") (pintype "bidirectional+no_connect"))
    )
    (net (code "66") (name "unconnected-(USB1-Holder-Pad5)") (class "Default")
      (node (ref "USB1") (pin "5") (pinfunction "Holder_5") (pintype "passive+no_connect"))
    )
    (net (code "67") (name "unconnected-(USB1-Holder-Pad6)") (class "Default")
      (node (ref "USB1") (pin "6") (pinfunction "Holder_6") (pintype "passive+no_connect"))
    )
  )
)
